# HSensor.net
KiCad netlist of a schematic drawn in Altium Designer
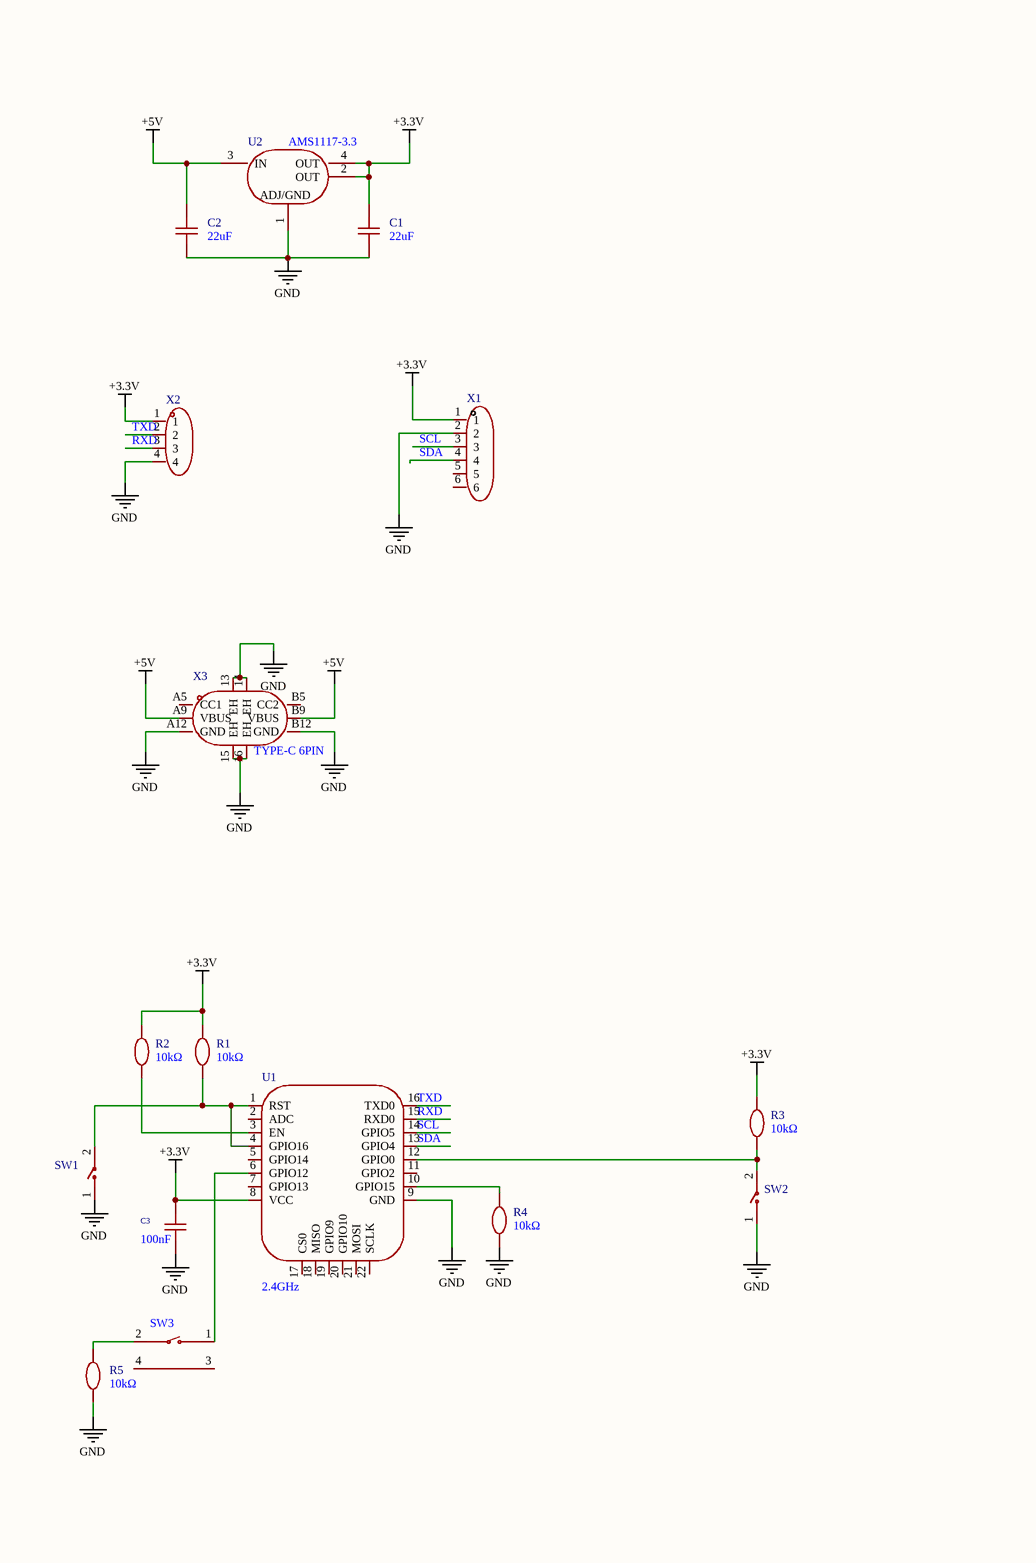
[diagram p0: HSensor.schdoc]

(export (version "E")
  (design (tool "Eeschema 10.0.6"))
  (components
    (comp (ref "C1")
      (value "22uF")
      (footprint "C1206")
      (fields
        (field (name "MANUFACTURER") "SAMSUNG(三星)")
        (field (name "MANUFACTURER PART") "CL31A226KOHNNNE")
        (field (name "TOLERANCE") "±10%")
      )
      (libsource (lib "altium-import") (part "root_1_CL31A226KOHNNNE_"))
    )
    (comp (ref "C2")
      (value "22uF")
      (footprint "C1206")
      (fields
        (field (name "MANUFACTURER") "SAMSUNG(三星)")
        (field (name "MANUFACTURER PART") "CL31A226KOHNNNE")
        (field (name "TOLERANCE") "±10%")
      )
      (libsource (lib "altium-import") (part "root_1_CL31A226KOHNNNE_"))
    )
    (comp (ref "C3")
      (value "100nF")
      (footprint "C0603")
      (fields
        (field (name "MANUFACTURER") "YAGEO(国巨)")
        (field (name "MANUFACTURER PART") "CC0603KRX7R9BB104")
        (field (name "TOLERANCE") "±10%")
      )
      (libsource (lib "altium-import") (part "root_1_CC0603KRX7R9BB104_"))
    )
    (comp (ref "R1")
      (value "10kΩ")
      (footprint "R0805")
      (fields
        (field (name "MANUFACTURER") "FOJAN(富捷)")
        (field (name "MANUFACTURER PART") "FRC0805J103TS")
        (field (name "TOLERANCE") "±5%")
      )
      (libsource (lib "altium-import") (part "root_1_FRC0805J103TS_"))
    )
    (comp (ref "R2")
      (value "10kΩ")
      (footprint "R0805")
      (fields
        (field (name "MANUFACTURER") "FOJAN(富捷)")
        (field (name "MANUFACTURER PART") "FRC0805J103TS")
        (field (name "TOLERANCE") "±5%")
      )
      (libsource (lib "altium-import") (part "root_1_FRC0805J103TS_"))
    )
    (comp (ref "R3")
      (value "10kΩ")
      (footprint "R0805")
      (fields
        (field (name "MANUFACTURER") "FOJAN(富捷)")
        (field (name "MANUFACTURER PART") "FRC0805J103TS")
        (field (name "TOLERANCE") "±5%")
      )
      (libsource (lib "altium-import") (part "root_1_FRC0805J103TS_"))
    )
    (comp (ref "R4")
      (value "10kΩ")
      (footprint "R0805")
      (fields
        (field (name "MANUFACTURER") "FOJAN(富捷)")
        (field (name "MANUFACTURER PART") "FRC0805J103TS")
        (field (name "TOLERANCE") "±5%")
      )
      (libsource (lib "altium-import") (part "root_1_FRC0805J103TS_"))
    )
    (comp (ref "R5")
      (value "10kΩ")
      (footprint "R0805")
      (fields
        (field (name "MANUFACTURER") "FOJAN(富捷)")
        (field (name "MANUFACTURER PART") "FRC0805J103TS")
        (field (name "TOLERANCE") "±5%")
      )
      (libsource (lib "altium-import") (part "root_1_mirrored_FRC0805J103TS_"))
    )
    (comp (ref "SW1")
      (value "TS-3025-A-C-A")
      (footprint "SW-SMD_L3.0-W2.5-P3.40-LS4.0-EH")
      (fields (field (name "MANUFACTURER") "XKB Connection(中国星坤)"))
      (libsource (lib "altium-import") (part "root_1_TS-3025-A-C-A_"))
    )
    (comp (ref "SW2")
      (value "TS-3025-A-C-A")
      (footprint "SW-SMD_L3.0-W2.5-P3.40-LS4.0-EH")
      (fields (field (name "MANUFACTURER") "XKB Connection(中国星坤)"))
      (libsource (lib "altium-import") (part "root_1_TS-3025-A-C-A_"))
    )
    (comp (ref "SW3")
      (value "KAN3543-0351C1-29/449")
      (footprint "SW-SMD_GANGYUAN_KAN3543-0351C1")
      (fields (field (name "MANUFACTURER") "GANGYUAN(港源)"))
      (libsource (lib "altium-import") (part "root_0_mirrored_KAN3543-0351C1-29/449_"))
    )
    (comp (ref "U1")
      (value "2.4GHz")
      (footprint "WIFIM-SMD_ESP-12F-ESP8266MOD")
      (fields
        (field (name "MANUFACTURER") "Ai-Thinker(安信可)")
        (field (name "MANUFACTURER PART") "ESP-12F(ESP8266MOD)")
      )
      (libsource (lib "altium-import") (part "root_0_ESP-12F(ESP8266MOD)_"))
    )
    (comp (ref "U2")
      (value "AMS1117-3.3")
      (footprint "SOT-223-3_L6.4-W3.5-P2.30-LS7.0-BR")
      (fields (field (name "MANUFACTURER") "国芯佳品"))
      (libsource (lib "altium-import") (part "root_0_AMS1117-3.3_"))
    )
    (comp (ref "X1")
      (value "PZ2.54-1*6-FWZ")
      (footprint "HDR-TH_6P-P2.54-H-M-W8.6-N")
      (fields (field (name "MANUFACTURER") "ZHOURI(洲日)"))
      (libsource (lib "altium-import") (part "root_0_PZ2.54-1*6-FWZ_"))
    )
    (comp (ref "X2")
      (value "PZ2.54-1x4-11.2")
      (footprint "HDR-TH_4P-P2.54-V-M")
      (fields (field (name "MANUFACTURER") "ZHOURI(洲日)"))
      (libsource (lib "altium-import") (part "root_0_PZ2.54-1x4-11.2_"))
    )
    (comp (ref "X3")
      (value "TYPE-C 6PIN")
      (footprint "USB-C-SMD_HX-TYPE-C-6PIN")
      (fields (field (name "MANUFACTURER") "hanxia(韩下)"))
      (libsource (lib "altium-import") (part "root_0_HX TYPE-C 6PIN_"))
    )
  )
  (nets
    (net (code "1") (name "+3.3V") (class "Default")
      (node (ref "C1") (pin "2") (pinfunction "2_2") (pintype "passive"))
      (node (ref "C3") (pin "2") (pinfunction "2_2") (pintype "passive"))
      (node (ref "R1") (pin "2") (pinfunction "2_2") (pintype "passive"))
      (node (ref "R2") (pin "2") (pinfunction "2_2") (pintype "passive"))
      (node (ref "R3") (pin "2") (pinfunction "2_2") (pintype "passive"))
      (node (ref "U1") (pin "8") (pinfunction "VCC_8") (pintype "passive"))
      (node (ref "U2") (pin "2") (pinfunction "OUT_2") (pintype "passive"))
      (node (ref "U2") (pin "4") (pinfunction "OUT_4") (pintype "passive"))
      (node (ref "X1") (pin "1") (pinfunction "1_1") (pintype "passive"))
      (node (ref "X2") (pin "1") (pinfunction "1_1") (pintype "passive"))
    )
    (net (code "2") (name "+5V") (class "Default")
      (node (ref "C2") (pin "2") (pinfunction "2_2") (pintype "passive"))
      (node (ref "U2") (pin "3") (pinfunction "IN_3") (pintype "passive"))
      (node (ref "X3") (pin "A9") (pinfunction "VBUS_A9") (pintype "passive"))
      (node (ref "X3") (pin "B9") (pinfunction "VBUS_B9") (pintype "passive"))
    )
    (net (code "3") (name "/RXD") (class "Default")
      (node (ref "U1") (pin "15") (pinfunction "RXD0_15") (pintype "passive"))
      (node (ref "X2") (pin "3") (pinfunction "3_3") (pintype "passive"))
    )
    (net (code "4") (name "/SCL") (class "Default")
      (node (ref "U1") (pin "14") (pinfunction "GPIO5_14") (pintype "passive"))
      (node (ref "X1") (pin "3") (pinfunction "3_3") (pintype "passive"))
    )
    (net (code "5") (name "/SDA") (class "Default")
      (node (ref "U1") (pin "13") (pinfunction "GPIO4_13") (pintype "passive"))
      (node (ref "X1") (pin "4") (pinfunction "4_4") (pintype "passive"))
    )
    (net (code "6") (name "/TXD") (class "Default")
      (node (ref "U1") (pin "16") (pinfunction "TXD0_16") (pintype "passive"))
      (node (ref "X2") (pin "2") (pinfunction "2_2") (pintype "passive"))
    )
    (net (code "7") (name "GND") (class "Default")
      (node (ref "C1") (pin "1") (pinfunction "1_1") (pintype "passive"))
      (node (ref "C2") (pin "1") (pinfunction "1_1") (pintype "passive"))
      (node (ref "C3") (pin "1") (pinfunction "1_1") (pintype "passive"))
      (node (ref "R4") (pin "1") (pinfunction "1_1") (pintype "passive"))
      (node (ref "R5") (pin "1") (pinfunction "1_1") (pintype "passive"))
      (node (ref "SW1") (pin "1") (pinfunction "1_1") (pintype "passive"))
      (node (ref "SW2") (pin "1") (pinfunction "1_1") (pintype "passive"))
      (node (ref "U1") (pin "9") (pinfunction "GND_9") (pintype "passive"))
      (node (ref "U2") (pin "1") (pinfunction "ADJ/GND_1") (pintype "passive"))
      (node (ref "X1") (pin "2") (pinfunction "2_2") (pintype "passive"))
      (node (ref "X2") (pin "4") (pinfunction "4_4") (pintype "passive"))
      (node (ref "X3") (pin "13") (pinfunction "EH_13") (pintype "passive"))
      (node (ref "X3") (pin "14") (pinfunction "EH_14") (pintype "passive"))
      (node (ref "X3") (pin "15") (pinfunction "EH_15") (pintype "passive"))
      (node (ref "X3") (pin "16") (pinfunction "EH_16") (pintype "passive"))
      (node (ref "X3") (pin "A12") (pinfunction "GND_A12") (pintype "passive"))
      (node (ref "X3") (pin "B12") (pinfunction "GND_B12") (pintype "passive"))
    )
    (net (code "8") (name "Net-(R5-Pad2)") (class "Default")
      (node (ref "R5") (pin "2") (pinfunction "2_2") (pintype "passive"))
      (node (ref "SW3") (pin "2") (pinfunction "2_2") (pintype "passive"))
    )
    (net (code "9") (name "Net-(U1-EN)") (class "Default")
      (node (ref "R2") (pin "1") (pinfunction "1_1") (pintype "passive"))
      (node (ref "U1") (pin "3") (pinfunction "EN_3") (pintype "passive"))
    )
    (net (code "10") (name "Net-(U1-GPIO0)") (class "Default")
      (node (ref "R3") (pin "1") (pinfunction "1_1") (pintype "passive"))
      (node (ref "SW2") (pin "2") (pinfunction "2_2") (pintype "passive"))
      (node (ref "U1") (pin "12") (pinfunction "GPIO0_12") (pintype "passive"))
    )
    (net (code "11") (name "Net-(U1-GPIO12)") (class "Default")
      (node (ref "SW3") (pin "1") (pinfunction "1_1") (pintype "passive"))
      (node (ref "U1") (pin "6") (pinfunction "GPIO12_6") (pintype "passive"))
    )
    (net (code "12") (name "Net-(U1-GPIO15)") (class "Default")
      (node (ref "R4") (pin "2") (pinfunction "2_2") (pintype "passive"))
      (node (ref "U1") (pin "10") (pinfunction "GPIO15_10") (pintype "passive"))
    )
    (net (code "13") (name "Net-(U1-GPIO16)") (class "Default")
      (node (ref "R1") (pin "1") (pinfunction "1_1") (pintype "passive"))
      (node (ref "SW1") (pin "2") (pinfunction "2_2") (pintype "passive"))
      (node (ref "U1") (pin "1") (pinfunction "RST_1") (pintype "passive"))
      (node (ref "U1") (pin "4") (pinfunction "GPIO16_4") (pintype "passive"))
    )
    (net (code "14") (name "unconnected-(SW3-Pad3)") (class "Default")
      (node (ref "SW3") (pin "3") (pinfunction "3_3") (pintype "passive"))
    )
    (net (code "15") (name "unconnected-(SW3-Pad4)") (class "Default")
      (node (ref "SW3") (pin "4") (pinfunction "4_4") (pintype "passive"))
    )
    (net (code "16") (name "unconnected-(U1-ADC-Pad2)") (class "Default")
      (node (ref "U1") (pin "2") (pinfunction "ADC_2") (pintype "passive"))
    )
    (net (code "17") (name "unconnected-(U1-CS0-Pad17)") (class "Default")
      (node (ref "U1") (pin "17") (pinfunction "CS0_17") (pintype "passive"))
    )
    (net (code "18") (name "unconnected-(U1-GPIO2-Pad11)") (class "Default")
      (node (ref "U1") (pin "11") (pinfunction "GPIO2_11") (pintype "passive"))
    )
    (net (code "19") (name "unconnected-(U1-GPIO9-Pad19)") (class "Default")
      (node (ref "U1") (pin "19") (pinfunction "GPIO9_19") (pintype "passive"))
    )
    (net (code "20") (name "unconnected-(U1-GPIO10-Pad20)") (class "Default")
      (node (ref "U1") (pin "20") (pinfunction "GPIO10_20") (pintype "passive"))
    )
    (net (code "21") (name "unconnected-(U1-GPIO13-Pad7)") (class "Default")
      (node (ref "U1") (pin "7") (pinfunction "GPIO13_7") (pintype "passive"))
    )
    (net (code "22") (name "unconnected-(U1-GPIO14-Pad5)") (class "Default")
      (node (ref "U1") (pin "5") (pinfunction "GPIO14_5") (pintype "passive"))
    )
    (net (code "23") (name "unconnected-(U1-MISO-Pad18)") (class "Default")
      (node (ref "U1") (pin "18") (pinfunction "MISO_18") (pintype "passive"))
    )
    (net (code "24") (name "unconnected-(U1-MOSI-Pad21)") (class "Default")
      (node (ref "U1") (pin "21") (pinfunction "MOSI_21") (pintype "passive"))
    )
    (net (code "25") (name "unconnected-(U1-SCLK-Pad22)") (class "Default")
      (node (ref "U1") (pin "22") (pinfunction "SCLK_22") (pintype "passive"))
    )
    (net (code "26") (name "unconnected-(X1-Pad5)") (class "Default")
      (node (ref "X1") (pin "5") (pinfunction "5_5") (pintype "passive"))
    )
    (net (code "27") (name "unconnected-(X1-Pad6)") (class "Default")
      (node (ref "X1") (pin "6") (pinfunction "6_6") (pintype "passive"))
    )
    (net (code "28") (name "unconnected-(X3-CC1-PadA5)") (class "Default")
      (node (ref "X3") (pin "A5") (pinfunction "CC1_A5") (pintype "passive"))
    )
    (net (code "29") (name "unconnected-(X3-CC2-PadB5)") (class "Default")
      (node (ref "X3") (pin "B5") (pinfunction "CC2_B5") (pintype "passive"))
    )
  )
)
